# LoadCellAmplifier.net
KiCad netlist of a schematic drawn in Altium Designer
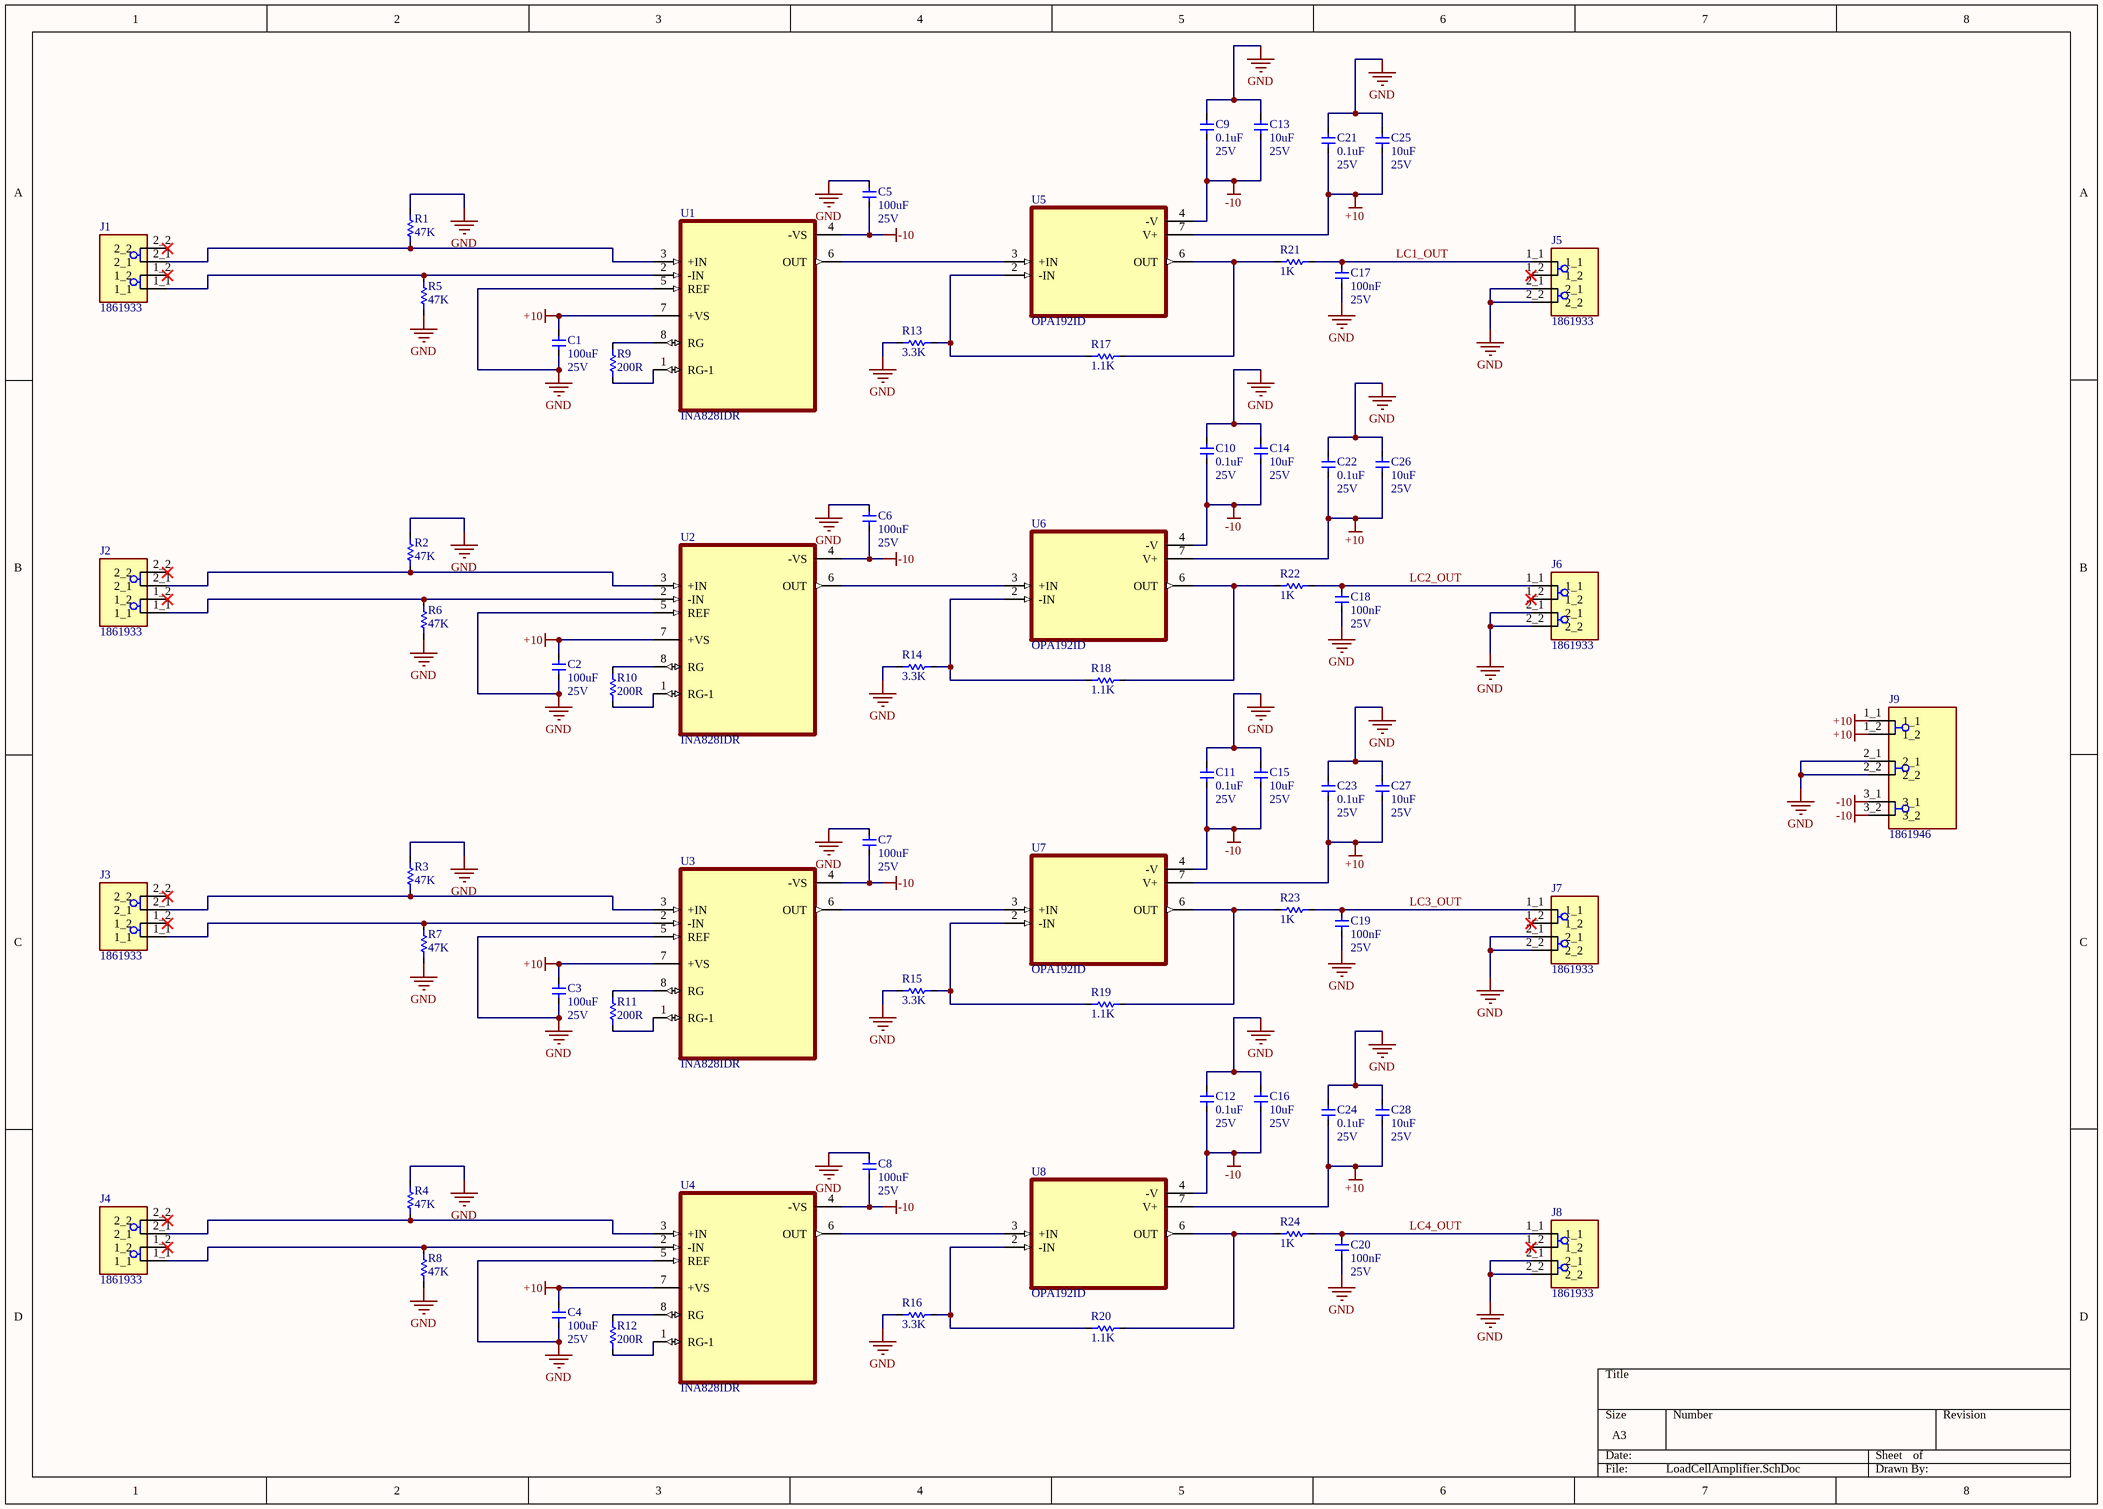
[diagram p0: LoadCellAmplifier.SchDoc]

(export (version "E")
  (design (tool "Eeschema 10.0.6"))
  (components
    (comp (ref "C1")
      (value "CGA3E2X7R1E104K080AA")
      (footprint "0603")
      (description "CAP CER 0.1UF 25V X7R 0603")
      (fields
        (field (name "MANUFACTURER") "TDK Corporation")
        (field (name "TOLERANCE") "±10%")
        (field (name "CAPACITANCE") "100uF")
        (field (name "VOLTAGE - RATED") "25V")
      )
      (libsource (lib "BioRocketSchematics") (part "CGA3E2X7R1E104K080AA"))
    )
    (comp (ref "C2")
      (value "CGA3E2X7R1E104K080AA")
      (footprint "0603")
      (description "CAP CER 0.1UF 25V X7R 0603")
      (fields
        (field (name "MANUFACTURER") "TDK Corporation")
        (field (name "TOLERANCE") "±10%")
        (field (name "CAPACITANCE") "100uF")
        (field (name "VOLTAGE - RATED") "25V")
      )
      (libsource (lib "BioRocketSchematics") (part "CGA3E2X7R1E104K080AA"))
    )
    (comp (ref "C3")
      (value "CGA3E2X7R1E104K080AA")
      (footprint "0603")
      (description "CAP CER 0.1UF 25V X7R 0603")
      (fields
        (field (name "MANUFACTURER") "TDK Corporation")
        (field (name "TOLERANCE") "±10%")
        (field (name "CAPACITANCE") "100uF")
        (field (name "VOLTAGE - RATED") "25V")
      )
      (libsource (lib "BioRocketSchematics") (part "CGA3E2X7R1E104K080AA"))
    )
    (comp (ref "C4")
      (value "CGA3E2X7R1E104K080AA")
      (footprint "0603")
      (description "CAP CER 0.1UF 25V X7R 0603")
      (fields
        (field (name "MANUFACTURER") "TDK Corporation")
        (field (name "TOLERANCE") "±10%")
        (field (name "CAPACITANCE") "100uF")
        (field (name "VOLTAGE - RATED") "25V")
      )
      (libsource (lib "BioRocketSchematics") (part "CGA3E2X7R1E104K080AA"))
    )
    (comp (ref "C5")
      (value "CGA3E2X7R1E104K080AA")
      (footprint "0603")
      (description "CAP CER 0.1UF 25V X7R 0603")
      (fields
        (field (name "MANUFACTURER") "TDK Corporation")
        (field (name "TOLERANCE") "±10%")
        (field (name "CAPACITANCE") "100uF")
        (field (name "VOLTAGE - RATED") "25V")
      )
      (libsource (lib "BioRocketSchematics") (part "CGA3E2X7R1E104K080AA"))
    )
    (comp (ref "C6")
      (value "CGA3E2X7R1E104K080AA")
      (footprint "0603")
      (description "CAP CER 0.1UF 25V X7R 0603")
      (fields
        (field (name "MANUFACTURER") "TDK Corporation")
        (field (name "TOLERANCE") "±10%")
        (field (name "CAPACITANCE") "100uF")
        (field (name "VOLTAGE - RATED") "25V")
      )
      (libsource (lib "BioRocketSchematics") (part "CGA3E2X7R1E104K080AA"))
    )
    (comp (ref "C7")
      (value "CGA3E2X7R1E104K080AA")
      (footprint "0603")
      (description "CAP CER 0.1UF 25V X7R 0603")
      (fields
        (field (name "MANUFACTURER") "TDK Corporation")
        (field (name "TOLERANCE") "±10%")
        (field (name "CAPACITANCE") "100uF")
        (field (name "VOLTAGE - RATED") "25V")
      )
      (libsource (lib "BioRocketSchematics") (part "CGA3E2X7R1E104K080AA"))
    )
    (comp (ref "C8")
      (value "CGA3E2X7R1E104K080AA")
      (footprint "0603")
      (description "CAP CER 0.1UF 25V X7R 0603")
      (fields
        (field (name "MANUFACTURER") "TDK Corporation")
        (field (name "TOLERANCE") "±10%")
        (field (name "CAPACITANCE") "100uF")
        (field (name "VOLTAGE - RATED") "25V")
      )
      (libsource (lib "BioRocketSchematics") (part "CGA3E2X7R1E104K080AA"))
    )
    (comp (ref "C9")
      (value "CGA3E2X7R1E104K080AA")
      (footprint "0603")
      (description "CAP CER 0.1UF 25V X7R 0603")
      (fields
        (field (name "MANUFACTURER") "TDK Corporation")
        (field (name "TOLERANCE") "±10%")
        (field (name "CAPACITANCE") "0.1uF")
        (field (name "VOLTAGE - RATED") "25V")
      )
      (libsource (lib "BioRocketSchematics") (part "CGA3E2X7R1E104K080AA"))
    )
    (comp (ref "C10")
      (value "CGA3E2X7R1E104K080AA")
      (footprint "0603")
      (description "CAP CER 0.1UF 25V X7R 0603")
      (fields
        (field (name "MANUFACTURER") "TDK Corporation")
        (field (name "TOLERANCE") "±10%")
        (field (name "CAPACITANCE") "0.1uF")
        (field (name "VOLTAGE - RATED") "25V")
      )
      (libsource (lib "BioRocketSchematics") (part "CGA3E2X7R1E104K080AA"))
    )
    (comp (ref "C11")
      (value "CGA3E2X7R1E104K080AA")
      (footprint "0603")
      (description "CAP CER 0.1UF 25V X7R 0603")
      (fields
        (field (name "MANUFACTURER") "TDK Corporation")
        (field (name "TOLERANCE") "±10%")
        (field (name "CAPACITANCE") "0.1uF")
        (field (name "VOLTAGE - RATED") "25V")
      )
      (libsource (lib "BioRocketSchematics") (part "CGA3E2X7R1E104K080AA"))
    )
    (comp (ref "C12")
      (value "CGA3E2X7R1E104K080AA")
      (footprint "0603")
      (description "CAP CER 0.1UF 25V X7R 0603")
      (fields
        (field (name "MANUFACTURER") "TDK Corporation")
        (field (name "TOLERANCE") "±10%")
        (field (name "CAPACITANCE") "0.1uF")
        (field (name "VOLTAGE - RATED") "25V")
      )
      (libsource (lib "BioRocketSchematics") (part "CGA3E2X7R1E104K080AA"))
    )
    (comp (ref "C13")
      (value "CGA3E2X7R1E104K080AA")
      (footprint "0603")
      (description "CAP CER 0.1UF 25V X7R 0603")
      (fields
        (field (name "MANUFACTURER") "TDK Corporation")
        (field (name "TOLERANCE") "±10%")
        (field (name "CAPACITANCE") "10uF")
        (field (name "VOLTAGE - RATED") "25V")
      )
      (libsource (lib "BioRocketSchematics") (part "CGA3E2X7R1E104K080AA"))
    )
    (comp (ref "C14")
      (value "CGA3E2X7R1E104K080AA")
      (footprint "0603")
      (description "CAP CER 0.1UF 25V X7R 0603")
      (fields
        (field (name "MANUFACTURER") "TDK Corporation")
        (field (name "TOLERANCE") "±10%")
        (field (name "CAPACITANCE") "10uF")
        (field (name "VOLTAGE - RATED") "25V")
      )
      (libsource (lib "BioRocketSchematics") (part "CGA3E2X7R1E104K080AA"))
    )
    (comp (ref "C15")
      (value "CGA3E2X7R1E104K080AA")
      (footprint "0603")
      (description "CAP CER 0.1UF 25V X7R 0603")
      (fields
        (field (name "MANUFACTURER") "TDK Corporation")
        (field (name "TOLERANCE") "±10%")
        (field (name "CAPACITANCE") "10uF")
        (field (name "VOLTAGE - RATED") "25V")
      )
      (libsource (lib "BioRocketSchematics") (part "CGA3E2X7R1E104K080AA"))
    )
    (comp (ref "C16")
      (value "CGA3E2X7R1E104K080AA")
      (footprint "0603")
      (description "CAP CER 0.1UF 25V X7R 0603")
      (fields
        (field (name "MANUFACTURER") "TDK Corporation")
        (field (name "TOLERANCE") "±10%")
        (field (name "CAPACITANCE") "10uF")
        (field (name "VOLTAGE - RATED") "25V")
      )
      (libsource (lib "BioRocketSchematics") (part "CGA3E2X7R1E104K080AA"))
    )
    (comp (ref "C17")
      (value "CGA3E2X7R1E104K080AA")
      (footprint "0603")
      (description "CAP CER 0.1UF 25V X7R 0603")
      (fields
        (field (name "MANUFACTURER") "TDK Corporation")
        (field (name "TOLERANCE") "±10%")
        (field (name "CAPACITANCE") "100nF")
        (field (name "VOLTAGE - RATED") "25V")
      )
      (libsource (lib "BioRocketSchematics") (part "CGA3E2X7R1E104K080AA"))
    )
    (comp (ref "C18")
      (value "CGA3E2X7R1E104K080AA")
      (footprint "0603")
      (description "CAP CER 0.1UF 25V X7R 0603")
      (fields
        (field (name "MANUFACTURER") "TDK Corporation")
        (field (name "TOLERANCE") "±10%")
        (field (name "CAPACITANCE") "100nF")
        (field (name "VOLTAGE - RATED") "25V")
      )
      (libsource (lib "BioRocketSchematics") (part "CGA3E2X7R1E104K080AA"))
    )
    (comp (ref "C19")
      (value "CGA3E2X7R1E104K080AA")
      (footprint "0603")
      (description "CAP CER 0.1UF 25V X7R 0603")
      (fields
        (field (name "MANUFACTURER") "TDK Corporation")
        (field (name "TOLERANCE") "±10%")
        (field (name "CAPACITANCE") "100nF")
        (field (name "VOLTAGE - RATED") "25V")
      )
      (libsource (lib "BioRocketSchematics") (part "CGA3E2X7R1E104K080AA"))
    )
    (comp (ref "C20")
      (value "CGA3E2X7R1E104K080AA")
      (footprint "0603")
      (description "CAP CER 0.1UF 25V X7R 0603")
      (fields
        (field (name "MANUFACTURER") "TDK Corporation")
        (field (name "TOLERANCE") "±10%")
        (field (name "CAPACITANCE") "100nF")
        (field (name "VOLTAGE - RATED") "25V")
      )
      (libsource (lib "BioRocketSchematics") (part "CGA3E2X7R1E104K080AA"))
    )
    (comp (ref "C21")
      (value "CGA3E2X7R1E104K080AA")
      (footprint "0603")
      (description "CAP CER 0.1UF 25V X7R 0603")
      (fields
        (field (name "MANUFACTURER") "TDK Corporation")
        (field (name "TOLERANCE") "±10%")
        (field (name "CAPACITANCE") "0.1uF")
        (field (name "VOLTAGE - RATED") "25V")
      )
      (libsource (lib "BioRocketSchematics") (part "CGA3E2X7R1E104K080AA"))
    )
    (comp (ref "C22")
      (value "CGA3E2X7R1E104K080AA")
      (footprint "0603")
      (description "CAP CER 0.1UF 25V X7R 0603")
      (fields
        (field (name "MANUFACTURER") "TDK Corporation")
        (field (name "TOLERANCE") "±10%")
        (field (name "CAPACITANCE") "0.1uF")
        (field (name "VOLTAGE - RATED") "25V")
      )
      (libsource (lib "BioRocketSchematics") (part "CGA3E2X7R1E104K080AA"))
    )
    (comp (ref "C23")
      (value "CGA3E2X7R1E104K080AA")
      (footprint "0603")
      (description "CAP CER 0.1UF 25V X7R 0603")
      (fields
        (field (name "MANUFACTURER") "TDK Corporation")
        (field (name "TOLERANCE") "±10%")
        (field (name "CAPACITANCE") "0.1uF")
        (field (name "VOLTAGE - RATED") "25V")
      )
      (libsource (lib "BioRocketSchematics") (part "CGA3E2X7R1E104K080AA"))
    )
    (comp (ref "C24")
      (value "CGA3E2X7R1E104K080AA")
      (footprint "0603")
      (description "CAP CER 0.1UF 25V X7R 0603")
      (fields
        (field (name "MANUFACTURER") "TDK Corporation")
        (field (name "TOLERANCE") "±10%")
        (field (name "CAPACITANCE") "0.1uF")
        (field (name "VOLTAGE - RATED") "25V")
      )
      (libsource (lib "BioRocketSchematics") (part "CGA3E2X7R1E104K080AA"))
    )
    (comp (ref "C25")
      (value "CGA3E2X7R1E104K080AA")
      (footprint "0603")
      (description "CAP CER 0.1UF 25V X7R 0603")
      (fields
        (field (name "MANUFACTURER") "TDK Corporation")
        (field (name "TOLERANCE") "±10%")
        (field (name "CAPACITANCE") "10uF")
        (field (name "VOLTAGE - RATED") "25V")
      )
      (libsource (lib "BioRocketSchematics") (part "CGA3E2X7R1E104K080AA"))
    )
    (comp (ref "C26")
      (value "CGA3E2X7R1E104K080AA")
      (footprint "0603")
      (description "CAP CER 0.1UF 25V X7R 0603")
      (fields
        (field (name "MANUFACTURER") "TDK Corporation")
        (field (name "TOLERANCE") "±10%")
        (field (name "CAPACITANCE") "10uF")
        (field (name "VOLTAGE - RATED") "25V")
      )
      (libsource (lib "BioRocketSchematics") (part "CGA3E2X7R1E104K080AA"))
    )
    (comp (ref "C27")
      (value "CGA3E2X7R1E104K080AA")
      (footprint "0603")
      (description "CAP CER 0.1UF 25V X7R 0603")
      (fields
        (field (name "MANUFACTURER") "TDK Corporation")
        (field (name "TOLERANCE") "±10%")
        (field (name "CAPACITANCE") "10uF")
        (field (name "VOLTAGE - RATED") "25V")
      )
      (libsource (lib "BioRocketSchematics") (part "CGA3E2X7R1E104K080AA"))
    )
    (comp (ref "C28")
      (value "CGA3E2X7R1E104K080AA")
      (footprint "0603")
      (description "CAP CER 0.1UF 25V X7R 0603")
      (fields
        (field (name "MANUFACTURER") "TDK Corporation")
        (field (name "TOLERANCE") "±10%")
        (field (name "CAPACITANCE") "10uF")
        (field (name "VOLTAGE - RATED") "25V")
      )
      (libsource (lib "BioRocketSchematics") (part "CGA3E2X7R1E104K080AA"))
    )
    (comp (ref "J1") (value "1861933") (footprint "PHOENIX_1861933") (libsource (lib "") (part "1861933_1")))
    (comp (ref "J2") (value "1861933") (footprint "PHOENIX_1861933") (libsource (lib "") (part "1861933_1")))
    (comp (ref "J3") (value "1861933") (footprint "PHOENIX_1861933") (libsource (lib "") (part "1861933_1")))
    (comp (ref "J4") (value "1861933") (footprint "PHOENIX_1861933") (libsource (lib "") (part "1861933_1")))
    (comp (ref "J5")
      (value "1861933")
      (footprint "PHOENIX_1861933")
      (libsource (lib "BioRocketSchematics") (part "1861933"))
    )
    (comp (ref "J6")
      (value "1861933")
      (footprint "PHOENIX_1861933")
      (libsource (lib "BioRocketSchematics") (part "1861933"))
    )
    (comp (ref "J7")
      (value "1861933")
      (footprint "PHOENIX_1861933")
      (libsource (lib "BioRocketSchematics") (part "1861933"))
    )
    (comp (ref "J8")
      (value "1861933")
      (footprint "PHOENIX_1861933")
      (libsource (lib "BioRocketSchematics") (part "1861933"))
    )
    (comp (ref "J9")
      (value "1861946")
      (footprint "PHOENIX_1861946")
      (fields (field (name "MF") "{'manufacturer': u'Phoenix Contact'}"))
      (libsource (lib "BioRocketSchematics") (part "1861946"))
    )
    (comp (ref "R1")
      (value "ERJ-3GEYJ103V")
      (footprint "0603")
      (description "SMD Chip Resistor, 10 kOhm, ï¿½ 5%, 100 mW, 0603 [1608 Metric], Thick Film, General Purpose")
      (fields
        (field (name "TOLERANCE") "±5%")
        (field (name "MANUFACTURER") "Panasonic Electronic Components")
        (field (name "RESISTANCE") "47K")
      )
      (libsource (lib "BioRocketSchematics") (part "ERJ-3GEYJ103V"))
    )
    (comp (ref "R2")
      (value "ERJ-3GEYJ103V")
      (footprint "0603")
      (description "SMD Chip Resistor, 10 kOhm, ï¿½ 5%, 100 mW, 0603 [1608 Metric], Thick Film, General Purpose")
      (fields
        (field (name "TOLERANCE") "±5%")
        (field (name "MANUFACTURER") "Panasonic Electronic Components")
        (field (name "RESISTANCE") "47K")
      )
      (libsource (lib "BioRocketSchematics") (part "ERJ-3GEYJ103V"))
    )
    (comp (ref "R3")
      (value "ERJ-3GEYJ103V")
      (footprint "0603")
      (description "SMD Chip Resistor, 10 kOhm, ï¿½ 5%, 100 mW, 0603 [1608 Metric], Thick Film, General Purpose")
      (fields
        (field (name "TOLERANCE") "±5%")
        (field (name "MANUFACTURER") "Panasonic Electronic Components")
        (field (name "RESISTANCE") "47K")
      )
      (libsource (lib "BioRocketSchematics") (part "ERJ-3GEYJ103V"))
    )
    (comp (ref "R4")
      (value "ERJ-3GEYJ103V")
      (footprint "0603")
      (description "SMD Chip Resistor, 10 kOhm, ï¿½ 5%, 100 mW, 0603 [1608 Metric], Thick Film, General Purpose")
      (fields
        (field (name "TOLERANCE") "±5%")
        (field (name "MANUFACTURER") "Panasonic Electronic Components")
        (field (name "RESISTANCE") "47K")
      )
      (libsource (lib "BioRocketSchematics") (part "ERJ-3GEYJ103V"))
    )
    (comp (ref "R5")
      (value "ERJ-3GEYJ103V")
      (footprint "0603")
      (description "SMD Chip Resistor, 10 kOhm, ï¿½ 5%, 100 mW, 0603 [1608 Metric], Thick Film, General Purpose")
      (fields
        (field (name "TOLERANCE") "±5%")
        (field (name "MANUFACTURER") "Panasonic Electronic Components")
        (field (name "RESISTANCE") "47K")
      )
      (libsource (lib "BioRocketSchematics") (part "ERJ-3GEYJ103V"))
    )
    (comp (ref "R6")
      (value "ERJ-3GEYJ103V")
      (footprint "0603")
      (description "SMD Chip Resistor, 10 kOhm, ï¿½ 5%, 100 mW, 0603 [1608 Metric], Thick Film, General Purpose")
      (fields
        (field (name "TOLERANCE") "±5%")
        (field (name "MANUFACTURER") "Panasonic Electronic Components")
        (field (name "RESISTANCE") "47K")
      )
      (libsource (lib "BioRocketSchematics") (part "ERJ-3GEYJ103V"))
    )
    (comp (ref "R7")
      (value "ERJ-3GEYJ103V")
      (footprint "0603")
      (description "SMD Chip Resistor, 10 kOhm, ï¿½ 5%, 100 mW, 0603 [1608 Metric], Thick Film, General Purpose")
      (fields
        (field (name "TOLERANCE") "±5%")
        (field (name "MANUFACTURER") "Panasonic Electronic Components")
        (field (name "RESISTANCE") "47K")
      )
      (libsource (lib "BioRocketSchematics") (part "ERJ-3GEYJ103V"))
    )
    (comp (ref "R8")
      (value "ERJ-3GEYJ103V")
      (footprint "0603")
      (description "SMD Chip Resistor, 10 kOhm, ï¿½ 5%, 100 mW, 0603 [1608 Metric], Thick Film, General Purpose")
      (fields
        (field (name "TOLERANCE") "±5%")
        (field (name "MANUFACTURER") "Panasonic Electronic Components")
        (field (name "RESISTANCE") "47K")
      )
      (libsource (lib "BioRocketSchematics") (part "ERJ-3GEYJ103V"))
    )
    (comp (ref "R9")
      (value "ERJ-3GEYJ103V")
      (footprint "0603")
      (description "SMD Chip Resistor, 10 kOhm, ï¿½ 5%, 100 mW, 0603 [1608 Metric], Thick Film, General Purpose")
      (fields
        (field (name "TOLERANCE") "±5%")
        (field (name "MANUFACTURER") "Panasonic Electronic Components")
        (field (name "RESISTANCE") "200R")
      )
      (libsource (lib "BioRocketSchematics") (part "ERJ-3GEYJ103V"))
    )
    (comp (ref "R10")
      (value "ERJ-3GEYJ103V")
      (footprint "0603")
      (description "SMD Chip Resistor, 10 kOhm, ï¿½ 5%, 100 mW, 0603 [1608 Metric], Thick Film, General Purpose")
      (fields
        (field (name "TOLERANCE") "±5%")
        (field (name "MANUFACTURER") "Panasonic Electronic Components")
        (field (name "RESISTANCE") "200R")
      )
      (libsource (lib "BioRocketSchematics") (part "ERJ-3GEYJ103V"))
    )
    (comp (ref "R11")
      (value "ERJ-3GEYJ103V")
      (footprint "0603")
      (description "SMD Chip Resistor, 10 kOhm, ï¿½ 5%, 100 mW, 0603 [1608 Metric], Thick Film, General Purpose")
      (fields
        (field (name "TOLERANCE") "±5%")
        (field (name "MANUFACTURER") "Panasonic Electronic Components")
        (field (name "RESISTANCE") "200R")
      )
      (libsource (lib "BioRocketSchematics") (part "ERJ-3GEYJ103V"))
    )
    (comp (ref "R12")
      (value "ERJ-3GEYJ103V")
      (footprint "0603")
      (description "SMD Chip Resistor, 10 kOhm, ï¿½ 5%, 100 mW, 0603 [1608 Metric], Thick Film, General Purpose")
      (fields
        (field (name "TOLERANCE") "±5%")
        (field (name "MANUFACTURER") "Panasonic Electronic Components")
        (field (name "RESISTANCE") "200R")
      )
      (libsource (lib "BioRocketSchematics") (part "ERJ-3GEYJ103V"))
    )
    (comp (ref "R13")
      (value "ERJ-3GEYJ103V")
      (footprint "0603")
      (description "SMD Chip Resistor, 10 kOhm, ï¿½ 5%, 100 mW, 0603 [1608 Metric], Thick Film, General Purpose")
      (fields
        (field (name "TOLERANCE") "±5%")
        (field (name "MANUFACTURER") "Panasonic Electronic Components")
        (field (name "RESISTANCE") "3.3K")
      )
      (libsource (lib "BioRocketSchematics") (part "ERJ-3GEYJ103V"))
    )
    (comp (ref "R14")
      (value "ERJ-3GEYJ103V")
      (footprint "0603")
      (description "SMD Chip Resistor, 10 kOhm, ï¿½ 5%, 100 mW, 0603 [1608 Metric], Thick Film, General Purpose")
      (fields
        (field (name "TOLERANCE") "±5%")
        (field (name "MANUFACTURER") "Panasonic Electronic Components")
        (field (name "RESISTANCE") "3.3K")
      )
      (libsource (lib "BioRocketSchematics") (part "ERJ-3GEYJ103V"))
    )
    (comp (ref "R15")
      (value "ERJ-3GEYJ103V")
      (footprint "0603")
      (description "SMD Chip Resistor, 10 kOhm, ï¿½ 5%, 100 mW, 0603 [1608 Metric], Thick Film, General Purpose")
      (fields
        (field (name "TOLERANCE") "±5%")
        (field (name "MANUFACTURER") "Panasonic Electronic Components")
        (field (name "RESISTANCE") "3.3K")
      )
      (libsource (lib "BioRocketSchematics") (part "ERJ-3GEYJ103V"))
    )
    (comp (ref "R16")
      (value "ERJ-3GEYJ103V")
      (footprint "0603")
      (description "SMD Chip Resistor, 10 kOhm, ï¿½ 5%, 100 mW, 0603 [1608 Metric], Thick Film, General Purpose")
      (fields
        (field (name "TOLERANCE") "±5%")
        (field (name "MANUFACTURER") "Panasonic Electronic Components")
        (field (name "RESISTANCE") "3.3K")
      )
      (libsource (lib "BioRocketSchematics") (part "ERJ-3GEYJ103V"))
    )
    (comp (ref "R17")
      (value "ERJ-3GEYJ103V")
      (footprint "0603")
      (description "SMD Chip Resistor, 10 kOhm, ï¿½ 5%, 100 mW, 0603 [1608 Metric], Thick Film, General Purpose")
      (fields
        (field (name "TOLERANCE") "±5%")
        (field (name "MANUFACTURER") "Panasonic Electronic Components")
        (field (name "RESISTANCE") "1.1K")
      )
      (libsource (lib "BioRocketSchematics") (part "ERJ-3GEYJ103V"))
    )
    (comp (ref "R18")
      (value "ERJ-3GEYJ103V")
      (footprint "0603")
      (description "SMD Chip Resistor, 10 kOhm, ï¿½ 5%, 100 mW, 0603 [1608 Metric], Thick Film, General Purpose")
      (fields
        (field (name "TOLERANCE") "±5%")
        (field (name "MANUFACTURER") "Panasonic Electronic Components")
        (field (name "RESISTANCE") "1.1K")
      )
      (libsource (lib "BioRocketSchematics") (part "ERJ-3GEYJ103V"))
    )
    (comp (ref "R19")
      (value "ERJ-3GEYJ103V")
      (footprint "0603")
      (description "SMD Chip Resistor, 10 kOhm, ï¿½ 5%, 100 mW, 0603 [1608 Metric], Thick Film, General Purpose")
      (fields
        (field (name "TOLERANCE") "±5%")
        (field (name "MANUFACTURER") "Panasonic Electronic Components")
        (field (name "RESISTANCE") "1.1K")
      )
      (libsource (lib "BioRocketSchematics") (part "ERJ-3GEYJ103V"))
    )
    (comp (ref "R20")
      (value "ERJ-3GEYJ103V")
      (footprint "0603")
      (description "SMD Chip Resistor, 10 kOhm, ï¿½ 5%, 100 mW, 0603 [1608 Metric], Thick Film, General Purpose")
      (fields
        (field (name "TOLERANCE") "±5%")
        (field (name "MANUFACTURER") "Panasonic Electronic Components")
        (field (name "RESISTANCE") "1.1K")
      )
      (libsource (lib "BioRocketSchematics") (part "ERJ-3GEYJ103V"))
    )
    (comp (ref "R21")
      (value "ERJ-3GEYJ103V")
      (footprint "0603")
      (description "SMD Chip Resistor, 10 kOhm, ï¿½ 5%, 100 mW, 0603 [1608 Metric], Thick Film, General Purpose")
      (fields
        (field (name "TOLERANCE") "±5%")
        (field (name "MANUFACTURER") "Panasonic Electronic Components")
        (field (name "RESISTANCE") "1K")
      )
      (libsource (lib "BioRocketSchematics") (part "ERJ-3GEYJ103V"))
    )
    (comp (ref "R22")
      (value "ERJ-3GEYJ103V")
      (footprint "0603")
      (description "SMD Chip Resistor, 10 kOhm, ï¿½ 5%, 100 mW, 0603 [1608 Metric], Thick Film, General Purpose")
      (fields
        (field (name "TOLERANCE") "±5%")
        (field (name "MANUFACTURER") "Panasonic Electronic Components")
        (field (name "RESISTANCE") "1K")
      )
      (libsource (lib "BioRocketSchematics") (part "ERJ-3GEYJ103V"))
    )
    (comp (ref "R23")
      (value "ERJ-3GEYJ103V")
      (footprint "0603")
      (description "SMD Chip Resistor, 10 kOhm, ï¿½ 5%, 100 mW, 0603 [1608 Metric], Thick Film, General Purpose")
      (fields
        (field (name "TOLERANCE") "±5%")
        (field (name "MANUFACTURER") "Panasonic Electronic Components")
        (field (name "RESISTANCE") "1K")
      )
      (libsource (lib "BioRocketSchematics") (part "ERJ-3GEYJ103V"))
    )
    (comp (ref "R24")
      (value "ERJ-3GEYJ103V")
      (footprint "0603")
      (description "SMD Chip Resistor, 10 kOhm, ï¿½ 5%, 100 mW, 0603 [1608 Metric], Thick Film, General Purpose")
      (fields
        (field (name "TOLERANCE") "±5%")
        (field (name "MANUFACTURER") "Panasonic Electronic Components")
        (field (name "RESISTANCE") "1K")
      )
      (libsource (lib "BioRocketSchematics") (part "ERJ-3GEYJ103V"))
    )
    (comp (ref "U1")
      (value "INA828IDR")
      (footprint "SOIC127P599X175-8N")
      (description "50-Î¼V Offset, 7-nV/âˆšHz Noise, Low-Power, Precision Instrumentation Amplifier")
      (fields (field (name "MF") "Texas Instruments"))
      (libsource (lib "BioRocketSchematics") (part "INA828IDR"))
    )
    (comp (ref "U2")
      (value "INA828IDR")
      (footprint "SOIC127P599X175-8N")
      (description "50-Î¼V Offset, 7-nV/âˆšHz Noise, Low-Power, Precision Instrumentation Amplifier")
      (fields (field (name "MF") "Texas Instruments"))
      (libsource (lib "BioRocketSchematics") (part "INA828IDR"))
    )
    (comp (ref "U3")
      (value "INA828IDR")
      (footprint "SOIC127P599X175-8N")
      (description "50-Î¼V Offset, 7-nV/âˆšHz Noise, Low-Power, Precision Instrumentation Amplifier")
      (fields (field (name "MF") "Texas Instruments"))
      (libsource (lib "BioRocketSchematics") (part "INA828IDR"))
    )
    (comp (ref "U4")
      (value "INA828IDR")
      (footprint "SOIC127P599X175-8N")
      (description "50-Î¼V Offset, 7-nV/âˆšHz Noise, Low-Power, Precision Instrumentation Amplifier")
      (fields (field (name "MF") "Texas Instruments"))
      (libsource (lib "BioRocketSchematics") (part "INA828IDR"))
    )
    (comp (ref "U5")
      (value "OPA192ID")
      (footprint "SOIC127P599X175-8N")
      (description "High-Voltage, Rail-to-Rail Input/Output, 5ÂµV, 0.2ÂµV/ËšC, Precision Operational Amplifier")
      (fields (field (name "MF") "Texas Instruments"))
      (libsource (lib "BioRocketSchematics") (part "OPA192ID"))
    )
    (comp (ref "U6")
      (value "OPA192ID")
      (footprint "SOIC127P599X175-8N")
      (description "High-Voltage, Rail-to-Rail Input/Output, 5ÂµV, 0.2ÂµV/ËšC, Precision Operational Amplifier")
      (fields (field (name "MF") "Texas Instruments"))
      (libsource (lib "BioRocketSchematics") (part "OPA192ID"))
    )
    (comp (ref "U7")
      (value "OPA192ID")
      (footprint "SOIC127P599X175-8N")
      (description "High-Voltage, Rail-to-Rail Input/Output, 5ÂµV, 0.2ÂµV/ËšC, Precision Operational Amplifier")
      (fields (field (name "MF") "Texas Instruments"))
      (libsource (lib "BioRocketSchematics") (part "OPA192ID"))
    )
    (comp (ref "U8")
      (value "OPA192ID")
      (footprint "SOIC127P599X175-8N")
      (description "High-Voltage, Rail-to-Rail Input/Output, 5ÂµV, 0.2ÂµV/ËšC, Precision Operational Amplifier")
      (fields (field (name "MF") "Texas Instruments"))
      (libsource (lib "BioRocketSchematics") (part "OPA192ID"))
    )
  )
  (nets
    (net (code "1") (name "+10") (class "Default")
      (node (ref "C1") (pin "1") (pinfunction "1_1") (pintype "passive"))
      (node (ref "C2") (pin "1") (pinfunction "1_1") (pintype "passive"))
      (node (ref "C21") (pin "2") (pinfunction "2_2") (pintype "passive"))
      (node (ref "C22") (pin "2") (pinfunction "2_2") (pintype "passive"))
      (node (ref "C23") (pin "2") (pinfunction "2_2") (pintype "passive"))
      (node (ref "C24") (pin "2") (pinfunction "2_2") (pintype "passive"))
      (node (ref "C25") (pin "2") (pinfunction "2_2") (pintype "passive"))
      (node (ref "C26") (pin "2") (pinfunction "2_2") (pintype "passive"))
      (node (ref "C27") (pin "2") (pinfunction "2_2") (pintype "passive"))
      (node (ref "C28") (pin "2") (pinfunction "2_2") (pintype "passive"))
      (node (ref "C3") (pin "1") (pinfunction "1_1") (pintype "passive"))
      (node (ref "C4") (pin "1") (pinfunction "1_1") (pintype "passive"))
      (node (ref "J9") (pin "1_1") (pinfunction "1_1_1_1") (pintype "passive"))
      (node (ref "J9") (pin "1_2") (pinfunction "1_2_1_2") (pintype "passive"))
      (node (ref "U1") (pin "7") (pinfunction "+VS_7") (pintype "power_in"))
      (node (ref "U2") (pin "7") (pinfunction "+VS_7") (pintype "power_in"))
      (node (ref "U3") (pin "7") (pinfunction "+VS_7") (pintype "power_in"))
      (node (ref "U4") (pin "7") (pinfunction "+VS_7") (pintype "power_in"))
      (node (ref "U5") (pin "7") (pinfunction "V+_7") (pintype "power_in"))
      (node (ref "U6") (pin "7") (pinfunction "V+_7") (pintype "power_in"))
      (node (ref "U7") (pin "7") (pinfunction "V+_7") (pintype "power_in"))
      (node (ref "U8") (pin "7") (pinfunction "V+_7") (pintype "power_in"))
    )
    (net (code "2") (name "-10") (class "Default")
      (node (ref "C10") (pin "2") (pinfunction "2_2") (pintype "passive"))
      (node (ref "C11") (pin "2") (pinfunction "2_2") (pintype "passive"))
      (node (ref "C12") (pin "2") (pinfunction "2_2") (pintype "passive"))
      (node (ref "C13") (pin "2") (pinfunction "2_2") (pintype "passive"))
      (node (ref "C14") (pin "2") (pinfunction "2_2") (pintype "passive"))
      (node (ref "C15") (pin "2") (pinfunction "2_2") (pintype "passive"))
      (node (ref "C16") (pin "2") (pinfunction "2_2") (pintype "passive"))
      (node (ref "C5") (pin "2") (pinfunction "2_2") (pintype "passive"))
      (node (ref "C6") (pin "2") (pinfunction "2_2") (pintype "passive"))
      (node (ref "C7") (pin "2") (pinfunction "2_2") (pintype "passive"))
      (node (ref "C8") (pin "2") (pinfunction "2_2") (pintype "passive"))
      (node (ref "C9") (pin "2") (pinfunction "2_2") (pintype "passive"))
      (node (ref "J9") (pin "3_1") (pinfunction "3_1_3_1") (pintype "passive"))
      (node (ref "J9") (pin "3_2") (pinfunction "3_2_3_2") (pintype "passive"))
      (node (ref "U1") (pin "4") (pinfunction "-VS_4") (pintype "power_in"))
      (node (ref "U2") (pin "4") (pinfunction "-VS_4") (pintype "power_in"))
      (node (ref "U3") (pin "4") (pinfunction "-VS_4") (pintype "power_in"))
      (node (ref "U4") (pin "4") (pinfunction "-VS_4") (pintype "power_in"))
      (node (ref "U5") (pin "4") (pinfunction "-V_4") (pintype "power_in"))
      (node (ref "U6") (pin "4") (pinfunction "-V_4") (pintype "power_in"))
      (node (ref "U7") (pin "4") (pinfunction "-V_4") (pintype "power_in"))
      (node (ref "U8") (pin "4") (pinfunction "-V_4") (pintype "power_in"))
    )
    (net (code "3") (name "/LC1_OUT") (class "Default")
      (node (ref "C17") (pin "1") (pinfunction "1_1") (pintype "passive"))
      (node (ref "J5") (pin "1_1") (pinfunction "1_1_1_1") (pintype "passive"))
      (node (ref "R21") (pin "1") (pinfunction "1_1") (pintype "passive"))
    )
    (net (code "4") (name "/LC2_OUT") (class "Default")
      (node (ref "C18") (pin "1") (pinfunction "1_1") (pintype "passive"))
      (node (ref "J6") (pin "1_1") (pinfunction "1_1_1_1") (pintype "passive"))
      (node (ref "R22") (pin "1") (pinfunction "1_1") (pintype "passive"))
    )
    (net (code "5") (name "/LC3_OUT") (class "Default")
      (node (ref "C19") (pin "1") (pinfunction "1_1") (pintype "passive"))
      (node (ref "J7") (pin "1_1") (pinfunction "1_1_1_1") (pintype "passive"))
      (node (ref "R23") (pin "1") (pinfunction "1_1") (pintype "passive"))
    )
    (net (code "6") (name "/LC4_OUT") (class "Default")
      (node (ref "C20") (pin "1") (pinfunction "1_1") (pintype "passive"))
      (node (ref "J8") (pin "1_1") (pinfunction "1_1_1_1") (pintype "passive"))
      (node (ref "R24") (pin "1") (pinfunction "1_1") (pintype "passive"))
    )
    (net (code "7") (name "GND") (class "Default")
      (node (ref "C1") (pin "2") (pinfunction "2_2") (pintype "passive"))
      (node (ref "C10") (pin "1") (pinfunction "1_1") (pintype "passive"))
      (node (ref "C11") (pin "1") (pinfunction "1_1") (pintype "passive"))
      (node (ref "C12") (pin "1") (pinfunction "1_1") (pintype "passive"))
      (node (ref "C13") (pin "1") (pinfunction "1_1") (pintype "passive"))
      (node (ref "C14") (pin "1") (pinfunction "1_1") (pintype "passive"))
      (node (ref "C15") (pin "1") (pinfunction "1_1") (pintype "passive"))
      (node (ref "C16") (pin "1") (pinfunction "1_1") (pintype "passive"))
      (node (ref "C17") (pin "2") (pinfunction "2_2") (pintype "passive"))
      (node (ref "C18") (pin "2") (pinfunction "2_2") (pintype "passive"))
      (node (ref "C19") (pin "2") (pinfunction "2_2") (pintype "passive"))
      (node (ref "C2") (pin "2") (pinfunction "2_2") (pintype "passive"))
      (node (ref "C20") (pin "2") (pinfunction "2_2") (pintype "passive"))
      (node (ref "C21") (pin "1") (pinfunction "1_1") (pintype "passive"))
      (node (ref "C22") (pin "1") (pinfunction "1_1") (pintype "passive"))
      (node (ref "C23") (pin "1") (pinfunction "1_1") (pintype "passive"))
      (node (ref "C24") (pin "1") (pinfunction "1_1") (pintype "passive"))
      (node (ref "C25") (pin "1") (pinfunction "1_1") (pintype "passive"))
      (node (ref "C26") (pin "1") (pinfunction "1_1") (pintype "passive"))
      (node (ref "C27") (pin "1") (pinfunction "1_1") (pintype "passive"))
      (node (ref "C28") (pin "1") (pinfunction "1_1") (pintype "passive"))
      (node (ref "C3") (pin "2") (pinfunction "2_2") (pintype "passive"))
      (node (ref "C4") (pin "2") (pinfunction "2_2") (pintype "passive"))
      (node (ref "C5") (pin "1") (pinfunction "1_1") (pintype "passive"))
      (node (ref "C6") (pin "1") (pinfunction "1_1") (pintype "passive"))
      (node (ref "C7") (pin "1") (pinfunction "1_1") (pintype "passive"))
      (node (ref "C8") (pin "1") (pinfunction "1_1") (pintype "passive"))
      (node (ref "C9") (pin "1") (pinfunction "1_1") (pintype "passive"))
      (node (ref "J5") (pin "2_1") (pinfunction "2_1_2_1") (pintype "passive"))
      (node (ref "J5") (pin "2_2") (pinfunction "2_2_2_2") (pintype "passive"))
      (node (ref "J6") (pin "2_1") (pinfunction "2_1_2_1") (pintype "passive"))
      (node (ref "J6") (pin "2_2") (pinfunction "2_2_2_2") (pintype "passive"))
      (node (ref "J7") (pin "2_1") (pinfunction "2_1_2_1") (pintype "passive"))
      (node (ref "J7") (pin "2_2") (pinfunction "2_2_2_2") (pintype "passive"))
      (node (ref "J8") (pin "2_1") (pinfunction "2_1_2_1") (pintype "passive"))
      (node (ref "J8") (pin "2_2") (pinfunction "2_2_2_2") (pintype "passive"))
      (node (ref "J9") (pin "2_1") (pinfunction "2_1_2_1") (pintype "passive"))
      (node (ref "J9") (pin "2_2") (pinfunction "2_2_2_2") (pintype "passive"))
      (node (ref "R1") (pin "1") (pinfunction "1_1") (pintype "passive"))
      (node (ref "R13") (pin "1") (pinfunction "1_1") (pintype "passive"))
      (node (ref "R14") (pin "1") (pinfunction "1_1") (pintype "passive"))
      (node (ref "R15") (pin "1") (pinfunction "1_1") (pintype "passive"))
      (node (ref "R16") (pin "1") (pinfunction "1_1") (pintype "passive"))
      (node (ref "R2") (pin "1") (pinfunction "1_1") (pintype "passive"))
      (node (ref "R3") (pin "1") (pinfunction "1_1") (pintype "passive"))
      (node (ref "R4") (pin "1") (pinfunction "1_1") (pintype "passive"))
      (node (ref "R5") (pin "2") (pinfunction "2_2") (pintype "passive"))
      (node (ref "R6") (pin "2") (pinfunction "2_2") (pintype "passive"))
      (node (ref "R7") (pin "2") (pinfunction "2_2") (pintype "passive"))
      (node (ref "R8") (pin "2") (pinfunction "2_2") (pintype "passive"))
      (node (ref "U1") (pin "5") (pinfunction "REF_5") (pintype "input"))
      (node (ref "U2") (pin "5") (pinfunction "REF_5") (pintype "input"))
      (node (ref "U3") (pin "5") (pinfunction "REF_5") (pintype "input"))
      (node (ref "U4") (pin "5") (pinfunction "REF_5") (pintype "input"))
    )
    (net (code "8") (name "Net-(U1-+IN)") (class "Default")
      (node (ref "J1") (pin "2_1") (pinfunction "2_1_2_1") (pintype "passive"))
      (node (ref "R1") (pin "2") (pinfunction "2_2") (pintype "passive"))
      (node (ref "U1") (pin "3") (pinfunction "+IN_3") (pintype "input"))
    )
    (net (code "9") (name "Net-(U1--IN)") (class "Default")
      (node (ref "J1") (pin "1_1") (pinfunction "1_1_1_1") (pintype "passive"))
      (node (ref "R5") (pin "1") (pinfunction "1_1") (pintype "passive"))
      (node (ref "U1") (pin "2") (pinfunction "-IN_2") (pintype "input"))
    )
    (net (code "10") (name "Net-(U1-OUT)") (class "Default")
      (node (ref "U1") (pin "6") (pinfunction "OUT_6") (pintype "output"))
      (node (ref "U5") (pin "3") (pinfunction "+IN_3") (pintype "input"))
    )
    (net (code "11") (name "Net-(U1-RG)") (class "Default")
      (node (ref "R9") (pin "2") (pinfunction "2_2") (pintype "passive"))
      (node (ref "U1") (pin "8") (pinfunction "RG_8") (pintype "bidirectional"))
    )
    (net (code "12") (name "Net-(U1-RG-1)") (class "Default")
      (node (ref "R9") (pin "1") (pinfunction "1_1") (pintype "passive"))
      (node (ref "U1") (pin "1") (pinfunction "RG-1_1") (pintype "bidirectional"))
    )
    (net (code "13") (name "Net-(U2-+IN)") (class "Default")
      (node (ref "J2") (pin "2_1") (pinfunction "2_1_2_1") (pintype "passive"))
      (node (ref "R2") (pin "2") (pinfunction "2_2") (pintype "passive"))
      (node (ref "U2") (pin "3") (pinfunction "+IN_3") (pintype "input"))
    )
    (net (code "14") (name "Net-(U2--IN)") (class "Default")
      (node (ref "J2") (pin "1_1") (pinfunction "1_1_1_1") (pintype "passive"))
      (node (ref "R6") (pin "1") (pinfunction "1_1") (pintype "passive"))
      (node (ref "U2") (pin "2") (pinfunction "-IN_2") (pintype "input"))
    )
    (net (code "15") (name "Net-(U2-OUT)") (class "Default")
      (node (ref "U2") (pin "6") (pinfunction "OUT_6") (pintype "output"))
      (node (ref "U6") (pin "3") (pinfunction "+IN_3") (pintype "input"))
    )
    (net (code "16") (name "Net-(U2-RG)") (class "Default")
      (node (ref "R10") (pin "2") (pinfunction "2_2") (pintype "passive"))
      (node (ref "U2") (pin "8") (pinfunction "RG_8") (pintype "bidirectional"))
    )
    (net (code "17") (name "Net-(U2-RG-1)") (class "Default")
      (node (ref "R10") (pin "1") (pinfunction "1_1") (pintype "passive"))
      (node (ref "U2") (pin "1") (pinfunction "RG-1_1") (pintype "bidirectional"))
    )
    (net (code "18") (name "Net-(U3-+IN)") (class "Default")
      (node (ref "J3") (pin "2_1") (pinfunction "2_1_2_1") (pintype "passive"))
      (node (ref "R3") (pin "2") (pinfunction "2_2") (pintype "passive"))
      (node (ref "U3") (pin "3") (pinfunction "+IN_3") (pintype "input"))
    )
    (net (code "19") (name "Net-(U3--IN)") (class "Default")
      (node (ref "J3") (pin "1_1") (pinfunction "1_1_1_1") (pintype "passive"))
      (node (ref "R7") (pin "1") (pinfunction "1_1") (pintype "passive"))
      (node (ref "U3") (pin "2") (pinfunction "-IN_2") (pintype "input"))
    )
    (net (code "20") (name "Net-(U3-OUT)") (class "Default")
      (node (ref "U3") (pin "6") (pinfunction "OUT_6") (pintype "output"))
      (node (ref "U7") (pin "3") (pinfunction "+IN_3") (pintype "input"))
    )
    (net (code "21") (name "Net-(U3-RG)") (class "Default")
      (node (ref "R11") (pin "2") (pinfunction "2_2") (pintype "passive"))
      (node (ref "U3") (pin "8") (pinfunction "RG_8") (pintype "bidirectional"))
    )
    (net (code "22") (name "Net-(U3-RG-1)") (class "Default")
      (node (ref "R11") (pin "1") (pinfunction "1_1") (pintype "passive"))
      (node (ref "U3") (pin "1") (pinfunction "RG-1_1") (pintype "bidirectional"))
    )
    (net (code "23") (name "Net-(U4-+IN)") (class "Default")
      (node (ref "J4") (pin "2_1") (pinfunction "2_1_2_1") (pintype "passive"))
      (node (ref "R4") (pin "2") (pinfunction "2_2") (pintype "passive"))
      (node (ref "U4") (pin "3") (pinfunction "+IN_3") (pintype "input"))
    )
    (net (code "24") (name "Net-(U4--IN)") (class "Default")
      (node (ref "J4") (pin "1_1") (pinfunction "1_1_1_1") (pintype "passive"))
      (node (ref "R8") (pin "1") (pinfunction "1_1") (pintype "passive"))
      (node (ref "U4") (pin "2") (pinfunction "-IN_2") (pintype "input"))
    )
    (net (code "25") (name "Net-(U4-OUT)") (class "Default")
      (node (ref "U4") (pin "6") (pinfunction "OUT_6") (pintype "output"))
      (node (ref "U8") (pin "3") (pinfunction "+IN_3") (pintype "input"))
    )
    (net (code "26") (name "Net-(U4-RG)") (class "Default")
      (node (ref "R12") (pin "2") (pinfunction "2_2") (pintype "passive"))
      (node (ref "U4") (pin "8") (pinfunction "RG_8") (pintype "bidirectional"))
    )
    (net (code "27") (name "Net-(U4-RG-1)") (class "Default")
      (node (ref "R12") (pin "1") (pinfunction "1_1") (pintype "passive"))
      (node (ref "U4") (pin "1") (pinfunction "RG-1_1") (pintype "bidirectional"))
    )
    (net (code "28") (name "Net-(U5--IN)") (class "Default")
      (node (ref "R13") (pin "2") (pinfunction "2_2") (pintype "passive"))
      (node (ref "R17") (pin "2") (pinfunction "2_2") (pintype "passive"))
      (node (ref "U5") (pin "2") (pinfunction "-IN_2") (pintype "input"))
    )
    (net (code "29") (name "Net-(U5-OUT)") (class "Default")
      (node (ref "R17") (pin "1") (pinfunction "1_1") (pintype "passive"))
      (node (ref "R21") (pin "2") (pinfunction "2_2") (pintype "passive"))
      (node (ref "U5") (pin "6") (pinfunction "OUT_6") (pintype "output"))
    )
    (net (code "30") (name "Net-(U6--IN)") (class "Default")
      (node (ref "R14") (pin "2") (pinfunction "2_2") (pintype "passive"))
      (node (ref "R18") (pin "2") (pinfunction "2_2") (pintype "passive"))
      (node (ref "U6") (pin "2") (pinfunction "-IN_2") (pintype "input"))
    )
    (net (code "31") (name "Net-(U6-OUT)") (class "Default")
      (node (ref "R18") (pin "1") (pinfunction "1_1") (pintype "passive"))
      (node (ref "R22") (pin "2") (pinfunction "2_2") (pintype "passive"))
      (node (ref "U6") (pin "6") (pinfunction "OUT_6") (pintype "output"))
    )
    (net (code "32") (name "Net-(U7--IN)") (class "Default")
      (node (ref "R15") (pin "2") (pinfunction "2_2") (pintype "passive"))
      (node (ref "R19") (pin "2") (pinfunction "2_2") (pintype "passive"))
      (node (ref "U7") (pin "2") (pinfunction "-IN_2") (pintype "input"))
    )
    (net (code "33") (name "Net-(U7-OUT)") (class "Default")
      (node (ref "R19") (pin "1") (pinfunction "1_1") (pintype "passive"))
      (node (ref "R23") (pin "2") (pinfunction "2_2") (pintype "passive"))
      (node (ref "U7") (pin "6") (pinfunction "OUT_6") (pintype "output"))
    )
    (net (code "34") (name "Net-(U8--IN)") (class "Default")
      (node (ref "R16") (pin "2") (pinfunction "2_2") (pintype "passive"))
      (node (ref "R20") (pin "2") (pinfunction "2_2") (pintype "passive"))
      (node (ref "U8") (pin "2") (pinfunction "-IN_2") (pintype "input"))
    )
    (net (code "35") (name "Net-(U8-OUT)") (class "Default")
      (node (ref "R20") (pin "1") (pinfunction "1_1") (pintype "passive"))
      (node (ref "R24") (pin "2") (pinfunction "2_2") (pintype "passive"))
      (node (ref "U8") (pin "6") (pinfunction "OUT_6") (pintype "output"))
    )
    (net (code "36") (name "unconnected-(J1-Pad1_2)") (class "Default")
      (node (ref "J1") (pin "1_2") (pinfunction "1_2_1_2") (pintype "passive+no_connect"))
    )
    (net (code "37") (name "unconnected-(J1-Pad2_2)") (class "Default")
      (node (ref "J1") (pin "2_2") (pinfunction "2_2_2_2") (pintype "passive+no_connect"))
    )
    (net (code "38") (name "unconnected-(J2-Pad1_2)") (class "Default")
      (node (ref "J2") (pin "1_2") (pinfunction "1_2_1_2") (pintype "passive+no_connect"))
    )
    (net (code "39") (name "unconnected-(J2-Pad2_2)") (class "Default")
      (node (ref "J2") (pin "2_2") (pinfunction "2_2_2_2") (pintype "passive+no_connect"))
    )
    (net (code "40") (name "unconnected-(J3-Pad1_2)") (class "Default")
      (node (ref "J3") (pin "1_2") (pinfunction "1_2_1_2") (pintype "passive+no_connect"))
    )
    (net (code "41") (name "unconnected-(J3-Pad2_2)") (class "Default")
      (node (ref "J3") (pin "2_2") (pinfunction "2_2_2_2") (pintype "passive+no_connect"))
    )
    (net (code "42") (name "unconnected-(J4-Pad1_2)") (class "Default")
      (node (ref "J4") (pin "1_2") (pinfunction "1_2_1_2") (pintype "passive+no_connect"))
    )
    (net (code "43") (name "unconnected-(J4-Pad2_2)") (class "Default")
      (node (ref "J4") (pin "2_2") (pinfunction "2_2_2_2") (pintype "passive+no_connect"))
    )
    (net (code "44") (name "unconnected-(J5-Pad1_2)") (class "Default")
      (node (ref "J5") (pin "1_2") (pinfunction "1_2_1_2") (pintype "passive+no_connect"))
    )
    (net (code "45") (name "unconnected-(J6-Pad1_2)") (class "Default")
      (node (ref "J6") (pin "1_2") (pinfunction "1_2_1_2") (pintype "passive+no_connect"))
    )
    (net (code "46") (name "unconnected-(J7-Pad1_2)") (class "Default")
      (node (ref "J7") (pin "1_2") (pinfunction "1_2_1_2") (pintype "passive+no_connect"))
    )
    (net (code "47") (name "unconnected-(J8-Pad1_2)") (class "Default")
      (node (ref "J8") (pin "1_2") (pinfunction "1_2_1_2") (pintype "passive+no_connect"))
    )
  )
)
